# Main.net
KiCad netlist of a schematic drawn in Altium Designer
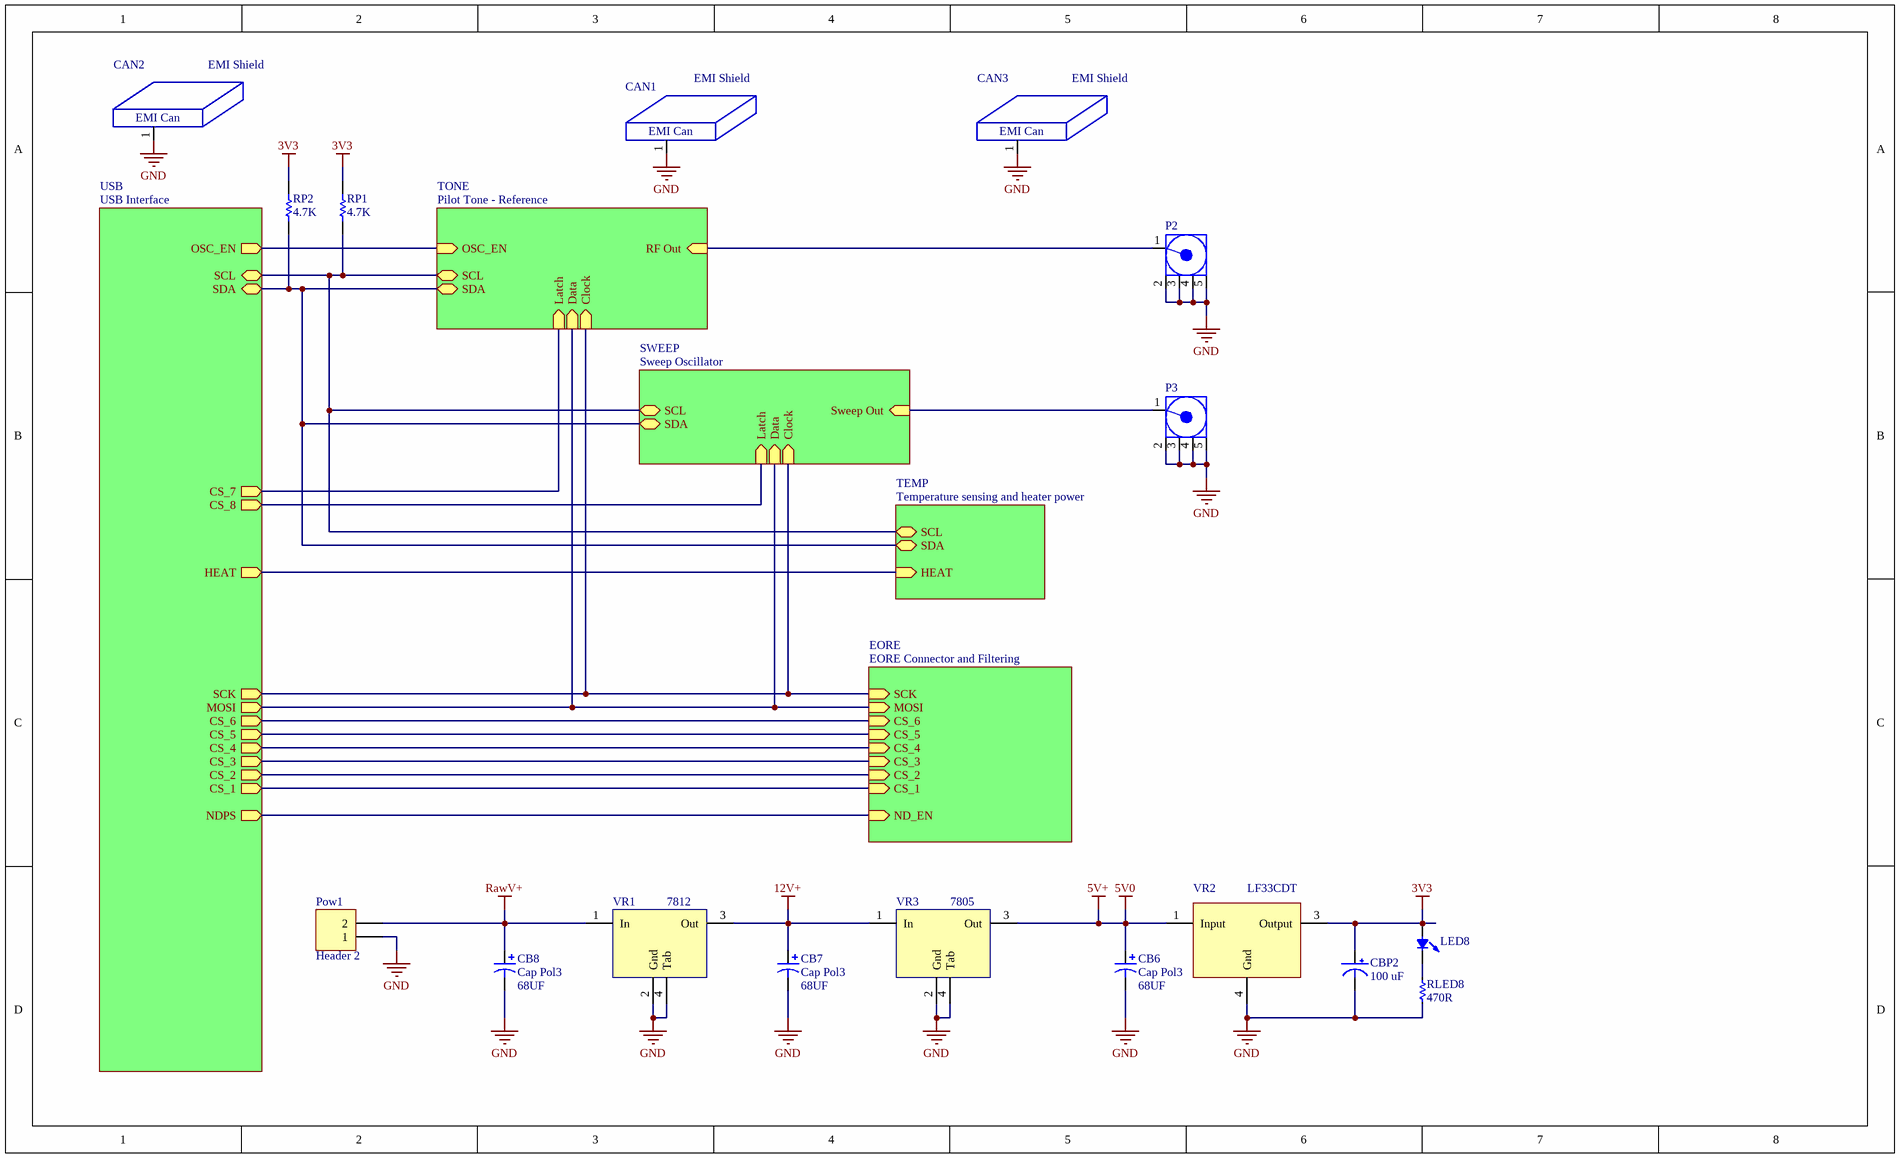
[diagram p0: Main.SchDoc]

(export (version "E")
  (design (tool "Eeschema 10.0.6"))
  (components
    (comp (ref "CAN1")
      (value "EMI Shield")
      (footprint "BMI-S-205-F")
      (description "Laird Technologies 2-part EMI can")
      (libsource (lib "RF Components") (part "BMI-S-205-F RF/EMI Can"))
    )
    (comp (ref "CAN2")
      (value "EMI Shield")
      (footprint "BMI-S-230-F")
      (description "Laird Technologies 2-part EMI can")
      (libsource (lib "RF Components") (part "BMI-S-230-F-R RF/EMI Can"))
    )
    (comp (ref "CAN3")
      (value "EMI Shield")
      (footprint "BMI-S-230-F")
      (description "Laird Technologies 2-part EMI can")
      (libsource (lib "RF Components") (part "BMI-S-230-F-R RF/EMI Can"))
    )
    (comp (ref "CB6")
      (value "Cap Pol3")
      (footprint "V")
      (description "KEMET T520 KO-CAP  Polymer SMT Tantalum")
      (fields (field (name "ALTIUM_VALUE") "68UF") (field (name "VOLTAGE") "10V"))
      (libsource (lib "Miscellaneous Devices") (part "Cap Pol3"))
    )
    (comp (ref "CB7")
      (value "Cap Pol3")
      (footprint "V")
      (description "KEMET T520 KO-CAP  Polymer SMT Tantalum")
      (fields (field (name "ALTIUM_VALUE") "68UF") (field (name "VOLTAGE") "10V"))
      (libsource (lib "Miscellaneous Devices") (part "Cap Pol3"))
    )
    (comp (ref "CB8")
      (value "Cap Pol3")
      (footprint "V")
      (description "KEMET T520 KO-CAP  Polymer SMT Tantalum")
      (fields (field (name "ALTIUM_VALUE") "68UF") (field (name "VOLTAGE") "10V"))
      (libsource (lib "Miscellaneous Devices") (part "Cap Pol3"))
    )
    (comp (ref "CBP2")
      (value "100 uF")
      (footprint "B")
      (libsource (lib "DAQ Sstem") (part "100 uf SMT Panasonic Cap"))
    )
    (comp (ref "LED8")
      (value "LED0")
      (footprint "0603 SMT LED")
      (description "T 1 3/4 LED")
      (fields (field (name "PUBLISHER") "Altium Limited"))
      (libsource (lib "Miscellaneous Devices") (part "LED0"))
    )
    (comp (ref "P2")
      (value "COAX-M")
      (footprint "SMA Jack - PCB Edge - MultiSize")
      (description "RF Coaxial PCB Connector, MMCX; Thru-Hole, Vertical Mount Plug,  50 Ohm Impedance")
      (fields (field (name "PUBLISHER") "Altium Limited"))
      (libsource (lib "Miscellaneous Connectors") (part "COAX-M"))
    )
    (comp (ref "P3")
      (value "COAX-M")
      (footprint "SMA Jack - PCB Edge - MultiSize")
      (description "RF Coaxial PCB Connector, MMCX; Thru-Hole, Vertical Mount Plug,  50 Ohm Impedance")
      (fields (field (name "PUBLISHER") "Altium Limited"))
      (libsource (lib "Miscellaneous Connectors") (part "COAX-M"))
    )
    (comp (ref "Pow1")
      (value "Header 2")
      (footprint "AMPModu MTE 2 Pin Shrouded Header")
      (description "Header, 2-Pin")
      (fields (field (name "PUBLISHER") "Altium Limited"))
      (libsource (lib "Miscellaneous Connectors") (part "Header 2"))
    )
    (comp (ref "RLED8")
      (value "470R")
      (footprint "0603R")
      (description "Semiconductor Resistor")
      (fields (field (name "Comment") "Res Semi Small") (field (name "PUBLISHER") "Altium Limited"))
      (libsource (lib "Miscellaneous Devices") (part "Res Semi Small"))
    )
    (comp (ref "RP1")
      (value "4.7K")
      (footprint "0603R")
      (description "Semiconductor Resistor")
      (fields (field (name "Comment") "Res Semi") (field (name "PUBLISHER") "Altium Limited"))
      (libsource (lib "Miscellaneous Devices") (part "Res Semi"))
    )
    (comp (ref "RP2")
      (value "4.7K")
      (footprint "0603R")
      (description "Semiconductor Resistor")
      (fields (field (name "Comment") "Res Semi") (field (name "PUBLISHER") "Altium Limited"))
      (libsource (lib "Miscellaneous Devices") (part "Res Semi"))
    )
    (comp (ref "VR1")
      (value "7812")
      (footprint "TO-220 - Small Heatsink")
      (description "1.2A Low-Dropout Voltage Regulator")
      (libsource (lib "ICs") (part "MIC2940"))
    )
    (comp (ref "VR2")
      (value "LF33CDT")
      (footprint "TO228P1000-3_4N")
      (description "Very low drop 500 ma voltage regulators")
      (libsource (lib "DAQ System") (part "LF33CDT"))
    )
    (comp (ref "VR3")
      (value "7805")
      (footprint "TO-220 - Small Heatsink")
      (description "1.2A Low-Dropout Voltage Regulator")
      (libsource (lib "ICs") (part "MIC2940"))
    )
  )
  (nets
    (net (code "13") (name "/RF Out") (class "Default")
      (node (ref "P2") (pin "1") (pinfunction "Signal_1") (pintype "passive"))
    )
    (net (code "15") (name "/SCL") (class "Default")
      (node (ref "RP1") (pin "1") (pinfunction "1_1") (pintype "passive"))
    )
    (net (code "16") (name "/SDA") (class "Default")
      (node (ref "RP2") (pin "1") (pinfunction "1_1") (pintype "passive"))
    )
    (net (code "17") (name "/Sweep Out") (class "Default")
      (node (ref "P3") (pin "1") (pinfunction "Signal_1") (pintype "passive"))
    )
    (net (code "18") (name "3V3") (class "Default")
      (node (ref "CBP2") (pin "1") (pinfunction "1_1") (pintype "passive"))
      (node (ref "LED8") (pin "1") (pinfunction "1_1") (pintype "passive"))
      (node (ref "RP1") (pin "2") (pinfunction "2_2") (pintype "passive"))
      (node (ref "RP2") (pin "2") (pinfunction "2_2") (pintype "passive"))
      (node (ref "VR2") (pin "3") (pinfunction "Output_3") (pintype "power_in"))
    )
    (net (code "19") (name "5V+") (class "Default")
      (node (ref "CB6") (pin "1") (pinfunction "1_1") (pintype "passive"))
      (node (ref "VR2") (pin "1") (pinfunction "Input_1") (pintype "power_in"))
      (node (ref "VR3") (pin "3") (pinfunction "Out_3") (pintype "power_in"))
    )
    (net (code "20") (name "12V+") (class "Default")
      (node (ref "CB7") (pin "1") (pinfunction "1_1") (pintype "passive"))
      (node (ref "VR1") (pin "3") (pinfunction "Out_3") (pintype "power_in"))
      (node (ref "VR3") (pin "1") (pinfunction "In_1") (pintype "power_in"))
    )
    (net (code "21") (name "GND") (class "Default")
      (node (ref "CAN1") (pin "1") (pintype "passive"))
      (node (ref "CAN2") (pin "1") (pintype "passive"))
      (node (ref "CAN3") (pin "1") (pintype "passive"))
      (node (ref "CB6") (pin "2") (pinfunction "2_2") (pintype "passive"))
      (node (ref "CB7") (pin "2") (pinfunction "2_2") (pintype "passive"))
      (node (ref "CB8") (pin "2") (pinfunction "2_2") (pintype "passive"))
      (node (ref "CBP2") (pin "2") (pinfunction "2_2") (pintype "passive"))
      (node (ref "P2") (pin "2") (pinfunction "GND_2") (pintype "power_in"))
      (node (ref "P2") (pin "3") (pinfunction "GND_3") (pintype "power_in"))
      (node (ref "P2") (pin "4") (pinfunction "GND_4") (pintype "power_in"))
      (node (ref "P2") (pin "5") (pinfunction "GND_5") (pintype "power_in"))
      (node (ref "P3") (pin "2") (pinfunction "GND_2") (pintype "power_in"))
      (node (ref "P3") (pin "3") (pinfunction "GND_3") (pintype "power_in"))
      (node (ref "P3") (pin "4") (pinfunction "GND_4") (pintype "power_in"))
      (node (ref "P3") (pin "5") (pinfunction "GND_5") (pintype "power_in"))
      (node (ref "Pow1") (pin "1") (pinfunction "1_1") (pintype "passive"))
      (node (ref "RLED8") (pin "2") (pinfunction "2_2") (pintype "passive"))
      (node (ref "VR1") (pin "2") (pinfunction "Gnd_2") (pintype "power_in"))
      (node (ref "VR1") (pin "4") (pinfunction "Tab_4") (pintype "power_in"))
      (node (ref "VR2") (pin "4") (pinfunction "Gnd_4") (pintype "power_in"))
      (node (ref "VR3") (pin "2") (pinfunction "Gnd_2") (pintype "power_in"))
      (node (ref "VR3") (pin "4") (pinfunction "Tab_4") (pintype "power_in"))
    )
    (net (code "22") (name "Net-(LED8-Pad2)") (class "Default")
      (node (ref "LED8") (pin "2") (pinfunction "2_2") (pintype "passive"))
      (node (ref "RLED8") (pin "1") (pinfunction "1_1") (pintype "passive"))
    )
    (net (code "23") (name "RawV+") (class "Default")
      (node (ref "CB8") (pin "1") (pinfunction "1_1") (pintype "passive"))
      (node (ref "Pow1") (pin "2") (pinfunction "2_2") (pintype "passive"))
      (node (ref "VR1") (pin "1") (pinfunction "In_1") (pintype "power_in"))
    )
  )
)
